# Pico_26Pin_Keyboard.net
KiCad netlist of a schematic drawn in EAGLE
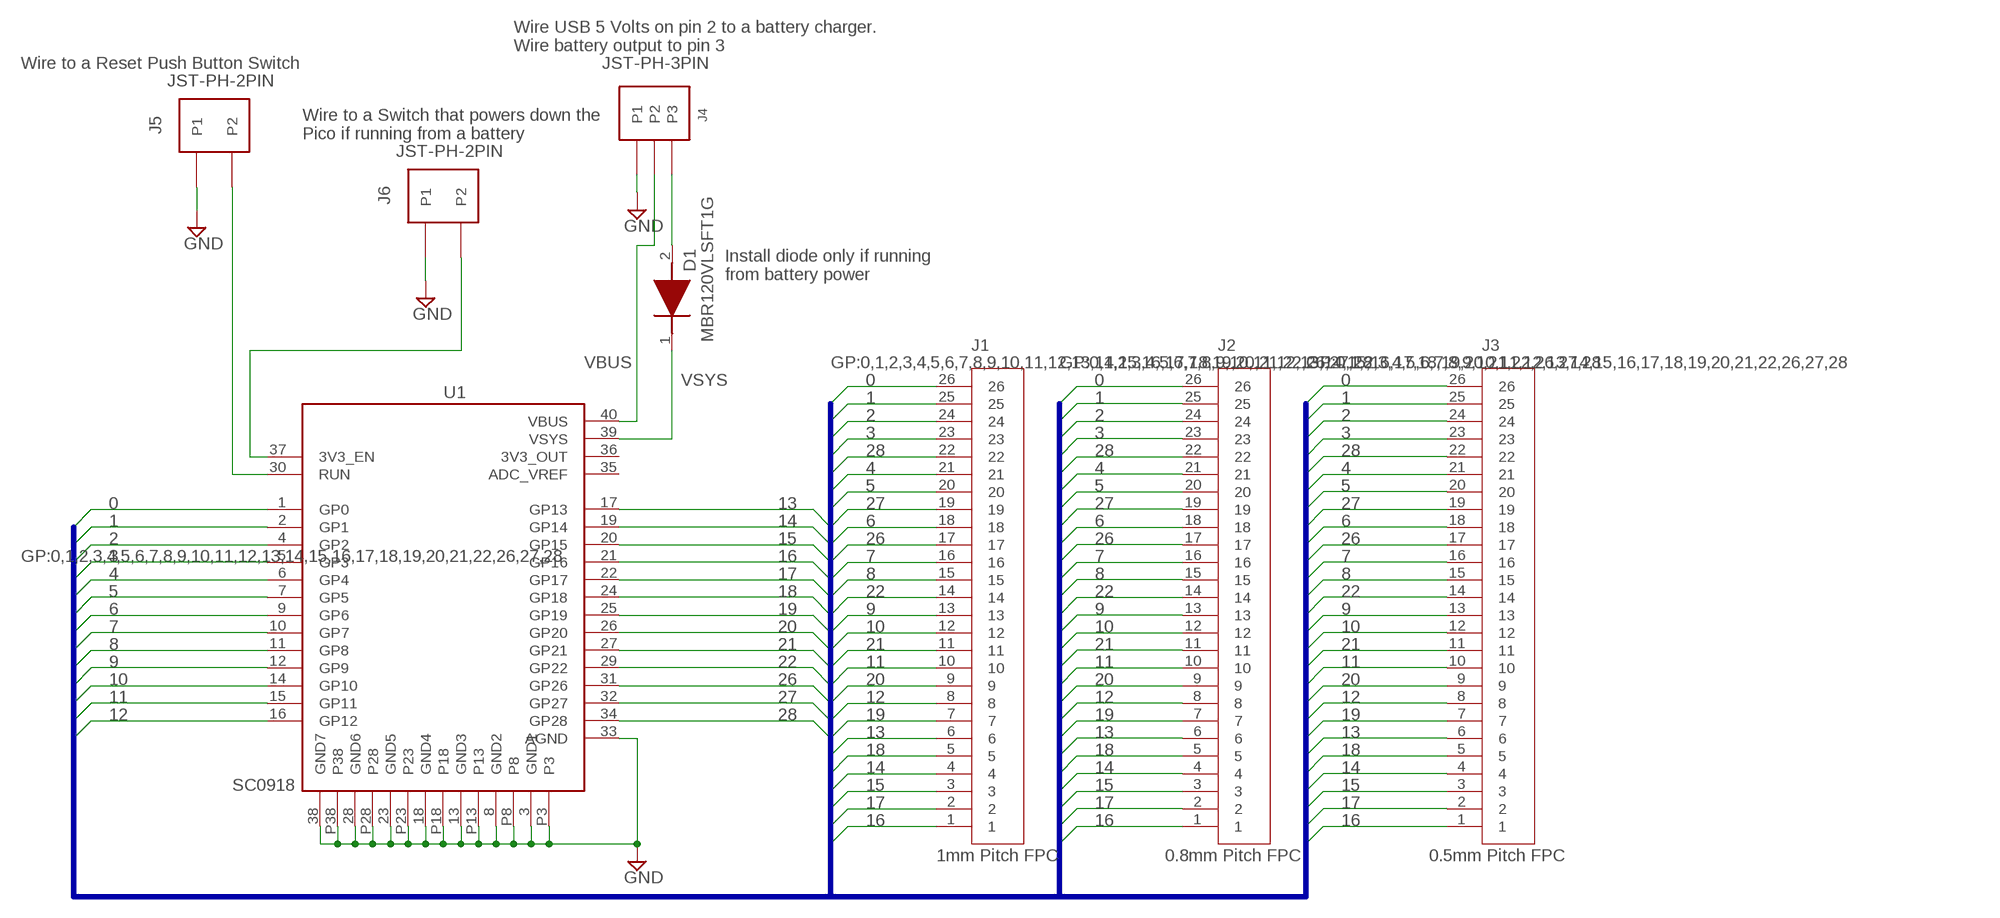
[diagram p0: schematic, sheet 1]

(export (version "E")
  (design (tool "Eeschema 10.0.6"))
  (components
    (comp (ref "D1")
      (value "MBR120VLSFT1G")
      (footprint "eagle-import:SODFL3616X98N")
      (fields (field (name "MOUSER_PART_NUMBER") "863-MBR120VLSFT1G"))
      (libsource (lib "eagle-import") (part "MBR120VLSFT1G"))
    )
    (comp (ref "J1")
      (value "1mm Pitch FPC")
      (footprint "eagle-import:FPC26")
      (libsource (lib "eagle-import") (part "FPC26"))
    )
    (comp (ref "J2")
      (value "0.8mm Pitch FPC")
      (footprint "eagle-import:FPC26_P8MM")
      (libsource (lib "eagle-import") (part "FPC26_P8MM"))
    )
    (comp (ref "J3")
      (value "0.5mm Pitch FPC")
      (footprint "eagle-import:FPC26_P5MM")
      (libsource (lib "eagle-import") (part "FPC26_P5MM"))
    )
    (comp (ref "J4")
      (value "JST-PH-3PIN")
      (footprint "eagle-import:JST-PH-3PIN")
      (libsource (lib "eagle-import") (part "JST-PH-3PIN"))
    )
    (comp (ref "J5")
      (value "JST-PH-2PIN")
      (footprint "eagle-import:JST-PH-2PIN")
      (libsource (lib "eagle-import") (part "JST-PH-2PIN"))
    )
    (comp (ref "J6")
      (value "JST-PH-2PIN")
      (footprint "eagle-import:JST-PH-2PIN")
      (libsource (lib "eagle-import") (part "JST-PH-2PIN"))
    )
    (comp (ref "U1")
      (value "SC0918")
      (footprint "eagle-import:MODULE_SC0918")
      (fields (field (name "MF") "Raspberry Pi"))
      (libsource (lib "eagle-import") (part "SC0918"))
    )
  )
  (nets
    (net (code "2") (name "/0") (class "Default")
      (node (ref "J1") (pin "26") (pinfunction "26_26") (pintype "bidirectional"))
      (node (ref "J2") (pin "26") (pinfunction "26_26") (pintype "bidirectional"))
      (node (ref "J3") (pin "26") (pinfunction "26_26") (pintype "bidirectional"))
      (node (ref "U1") (pin "1") (pinfunction "GP0_1") (pintype "bidirectional"))
    )
    (net (code "3") (name "/1") (class "Default")
      (node (ref "J1") (pin "25") (pinfunction "25_25") (pintype "bidirectional"))
      (node (ref "J2") (pin "25") (pinfunction "25_25") (pintype "bidirectional"))
      (node (ref "J3") (pin "25") (pinfunction "25_25") (pintype "bidirectional"))
      (node (ref "U1") (pin "2") (pinfunction "GP1_2") (pintype "bidirectional"))
    )
    (net (code "4") (name "/2") (class "Default")
      (node (ref "J1") (pin "24") (pinfunction "24_24") (pintype "bidirectional"))
      (node (ref "J2") (pin "24") (pinfunction "24_24") (pintype "bidirectional"))
      (node (ref "J3") (pin "24") (pinfunction "24_24") (pintype "bidirectional"))
      (node (ref "U1") (pin "4") (pinfunction "GP2_4") (pintype "bidirectional"))
    )
    (net (code "5") (name "/3") (class "Default")
      (node (ref "J1") (pin "23") (pinfunction "23_23") (pintype "bidirectional"))
      (node (ref "J2") (pin "23") (pinfunction "23_23") (pintype "bidirectional"))
      (node (ref "J3") (pin "23") (pinfunction "23_23") (pintype "bidirectional"))
      (node (ref "U1") (pin "5") (pinfunction "GP3_5") (pintype "bidirectional"))
    )
    (net (code "6") (name "/3V3_OUT") (class "Default")
      (node (ref "U1") (pin "36") (pinfunction "3V3_OUT_36") (pintype "power_in"))
    )
    (net (code "7") (name "/4") (class "Default")
      (node (ref "J1") (pin "21") (pinfunction "21_21") (pintype "bidirectional"))
      (node (ref "J2") (pin "21") (pinfunction "21_21") (pintype "bidirectional"))
      (node (ref "J3") (pin "21") (pinfunction "21_21") (pintype "bidirectional"))
      (node (ref "U1") (pin "6") (pinfunction "GP4_6") (pintype "bidirectional"))
    )
    (net (code "8") (name "/5") (class "Default")
      (node (ref "J1") (pin "20") (pinfunction "20_20") (pintype "bidirectional"))
      (node (ref "J2") (pin "20") (pinfunction "20_20") (pintype "bidirectional"))
      (node (ref "J3") (pin "20") (pinfunction "20_20") (pintype "bidirectional"))
      (node (ref "U1") (pin "7") (pinfunction "GP5_7") (pintype "bidirectional"))
    )
    (net (code "9") (name "/6") (class "Default")
      (node (ref "J1") (pin "18") (pinfunction "18_18") (pintype "bidirectional"))
      (node (ref "J2") (pin "18") (pinfunction "18_18") (pintype "bidirectional"))
      (node (ref "J3") (pin "18") (pinfunction "18_18") (pintype "bidirectional"))
      (node (ref "U1") (pin "9") (pinfunction "GP6_9") (pintype "bidirectional"))
    )
    (net (code "10") (name "/7") (class "Default")
      (node (ref "J1") (pin "16") (pinfunction "16_16") (pintype "bidirectional"))
      (node (ref "J2") (pin "16") (pinfunction "16_16") (pintype "bidirectional"))
      (node (ref "J3") (pin "16") (pinfunction "16_16") (pintype "bidirectional"))
      (node (ref "U1") (pin "10") (pinfunction "GP7_10") (pintype "bidirectional"))
    )
    (net (code "11") (name "/8") (class "Default")
      (node (ref "J1") (pin "15") (pinfunction "15_15") (pintype "bidirectional"))
      (node (ref "J2") (pin "15") (pinfunction "15_15") (pintype "bidirectional"))
      (node (ref "J3") (pin "15") (pinfunction "15_15") (pintype "bidirectional"))
      (node (ref "U1") (pin "11") (pinfunction "GP8_11") (pintype "bidirectional"))
    )
    (net (code "12") (name "/9") (class "Default")
      (node (ref "J1") (pin "13") (pinfunction "13_13") (pintype "bidirectional"))
      (node (ref "J2") (pin "13") (pinfunction "13_13") (pintype "bidirectional"))
      (node (ref "J3") (pin "13") (pinfunction "13_13") (pintype "bidirectional"))
      (node (ref "U1") (pin "12") (pinfunction "GP9_12") (pintype "bidirectional"))
    )
    (net (code "13") (name "/10") (class "Default")
      (node (ref "J1") (pin "12") (pinfunction "12_12") (pintype "bidirectional"))
      (node (ref "J2") (pin "12") (pinfunction "12_12") (pintype "bidirectional"))
      (node (ref "J3") (pin "12") (pinfunction "12_12") (pintype "bidirectional"))
      (node (ref "U1") (pin "14") (pinfunction "GP10_14") (pintype "bidirectional"))
    )
    (net (code "14") (name "/11") (class "Default")
      (node (ref "J1") (pin "10") (pinfunction "10_10") (pintype "bidirectional"))
      (node (ref "J2") (pin "10") (pinfunction "10_10") (pintype "bidirectional"))
      (node (ref "J3") (pin "10") (pinfunction "10_10") (pintype "bidirectional"))
      (node (ref "U1") (pin "15") (pinfunction "GP11_15") (pintype "bidirectional"))
    )
    (net (code "15") (name "/12") (class "Default")
      (node (ref "J1") (pin "8") (pinfunction "8_8") (pintype "bidirectional"))
      (node (ref "J2") (pin "8") (pinfunction "8_8") (pintype "bidirectional"))
      (node (ref "J3") (pin "8") (pinfunction "8_8") (pintype "bidirectional"))
      (node (ref "U1") (pin "16") (pinfunction "GP12_16") (pintype "bidirectional"))
    )
    (net (code "16") (name "/13") (class "Default")
      (node (ref "J1") (pin "6") (pinfunction "6_6") (pintype "bidirectional"))
      (node (ref "J2") (pin "6") (pinfunction "6_6") (pintype "bidirectional"))
      (node (ref "J3") (pin "6") (pinfunction "6_6") (pintype "bidirectional"))
      (node (ref "U1") (pin "17") (pinfunction "GP13_17") (pintype "bidirectional"))
    )
    (net (code "17") (name "/14") (class "Default")
      (node (ref "J1") (pin "4") (pinfunction "4_4") (pintype "bidirectional"))
      (node (ref "J2") (pin "4") (pinfunction "4_4") (pintype "bidirectional"))
      (node (ref "J3") (pin "4") (pinfunction "4_4") (pintype "bidirectional"))
      (node (ref "U1") (pin "19") (pinfunction "GP14_19") (pintype "bidirectional"))
    )
    (net (code "18") (name "/15") (class "Default")
      (node (ref "J1") (pin "3") (pinfunction "3_3") (pintype "bidirectional"))
      (node (ref "J2") (pin "3") (pinfunction "3_3") (pintype "bidirectional"))
      (node (ref "J3") (pin "3") (pinfunction "3_3") (pintype "bidirectional"))
      (node (ref "U1") (pin "20") (pinfunction "GP15_20") (pintype "bidirectional"))
    )
    (net (code "19") (name "/16") (class "Default")
      (node (ref "J1") (pin "1") (pinfunction "1_1") (pintype "bidirectional"))
      (node (ref "J2") (pin "1") (pinfunction "1_1") (pintype "bidirectional"))
      (node (ref "J3") (pin "1") (pinfunction "1_1") (pintype "bidirectional"))
      (node (ref "U1") (pin "21") (pinfunction "GP16_21") (pintype "bidirectional"))
    )
    (net (code "20") (name "/17") (class "Default")
      (node (ref "J1") (pin "2") (pinfunction "2_2") (pintype "bidirectional"))
      (node (ref "J2") (pin "2") (pinfunction "2_2") (pintype "bidirectional"))
      (node (ref "J3") (pin "2") (pinfunction "2_2") (pintype "bidirectional"))
      (node (ref "U1") (pin "22") (pinfunction "GP17_22") (pintype "bidirectional"))
    )
    (net (code "21") (name "/18") (class "Default")
      (node (ref "J1") (pin "5") (pinfunction "5_5") (pintype "bidirectional"))
      (node (ref "J2") (pin "5") (pinfunction "5_5") (pintype "bidirectional"))
      (node (ref "J3") (pin "5") (pinfunction "5_5") (pintype "bidirectional"))
      (node (ref "U1") (pin "24") (pinfunction "GP18_24") (pintype "bidirectional"))
    )
    (net (code "22") (name "/19") (class "Default")
      (node (ref "J1") (pin "7") (pinfunction "7_7") (pintype "bidirectional"))
      (node (ref "J2") (pin "7") (pinfunction "7_7") (pintype "bidirectional"))
      (node (ref "J3") (pin "7") (pinfunction "7_7") (pintype "bidirectional"))
      (node (ref "U1") (pin "25") (pinfunction "GP19_25") (pintype "bidirectional"))
    )
    (net (code "23") (name "/20") (class "Default")
      (node (ref "J1") (pin "9") (pinfunction "9_9") (pintype "bidirectional"))
      (node (ref "J2") (pin "9") (pinfunction "9_9") (pintype "bidirectional"))
      (node (ref "J3") (pin "9") (pinfunction "9_9") (pintype "bidirectional"))
      (node (ref "U1") (pin "26") (pinfunction "GP20_26") (pintype "bidirectional"))
    )
    (net (code "24") (name "/21") (class "Default")
      (node (ref "J1") (pin "11") (pinfunction "11_11") (pintype "bidirectional"))
      (node (ref "J2") (pin "11") (pinfunction "11_11") (pintype "bidirectional"))
      (node (ref "J3") (pin "11") (pinfunction "11_11") (pintype "bidirectional"))
      (node (ref "U1") (pin "27") (pinfunction "GP21_27") (pintype "bidirectional"))
    )
    (net (code "25") (name "/22") (class "Default")
      (node (ref "J1") (pin "14") (pinfunction "14_14") (pintype "bidirectional"))
      (node (ref "J2") (pin "14") (pinfunction "14_14") (pintype "bidirectional"))
      (node (ref "J3") (pin "14") (pinfunction "14_14") (pintype "bidirectional"))
      (node (ref "U1") (pin "29") (pinfunction "GP22_29") (pintype "bidirectional"))
    )
    (net (code "26") (name "/26") (class "Default")
      (node (ref "J1") (pin "17") (pinfunction "17_17") (pintype "bidirectional"))
      (node (ref "J2") (pin "17") (pinfunction "17_17") (pintype "bidirectional"))
      (node (ref "J3") (pin "17") (pinfunction "17_17") (pintype "bidirectional"))
      (node (ref "U1") (pin "31") (pinfunction "GP26_31") (pintype "bidirectional"))
    )
    (net (code "27") (name "/27") (class "Default")
      (node (ref "J1") (pin "19") (pinfunction "19_19") (pintype "bidirectional"))
      (node (ref "J2") (pin "19") (pinfunction "19_19") (pintype "bidirectional"))
      (node (ref "J3") (pin "19") (pinfunction "19_19") (pintype "bidirectional"))
      (node (ref "U1") (pin "32") (pinfunction "GP27_32") (pintype "bidirectional"))
    )
    (net (code "28") (name "/28") (class "Default")
      (node (ref "J1") (pin "22") (pinfunction "22_22") (pintype "bidirectional"))
      (node (ref "J2") (pin "22") (pinfunction "22_22") (pintype "bidirectional"))
      (node (ref "J3") (pin "22") (pinfunction "22_22") (pintype "bidirectional"))
      (node (ref "U1") (pin "34") (pinfunction "GP28_34") (pintype "bidirectional"))
    )
    (net (code "29") (name "/ADC_VREF") (class "Default")
      (node (ref "U1") (pin "35") (pinfunction "ADC_VREF_35") (pintype "power_in"))
    )
    (net (code "30") (name "/VBUS") (class "Default")
      (node (ref "J4") (pin "P$2") (pinfunction "P2_P$2") (pintype "bidirectional"))
      (node (ref "U1") (pin "40") (pinfunction "VBUS_40") (pintype "power_in"))
    )
    (net (code "31") (name "/VSYS") (class "Default")
      (node (ref "D1") (pin "1") (pinfunction "K_1") (pintype "bidirectional"))
      (node (ref "U1") (pin "39") (pinfunction "VSYS_39") (pintype "power_in"))
    )
    (net (code "33") (name "GND") (class "Default")
      (node (ref "J4") (pin "P$1") (pinfunction "P1_P$1") (pintype "bidirectional"))
      (node (ref "J5") (pin "P$1") (pinfunction "P1_P$1") (pintype "bidirectional"))
      (node (ref "J6") (pin "P$1") (pinfunction "P1_P$1") (pintype "bidirectional"))
      (node (ref "U1") (pin "13") (pinfunction "GND3_13") (pintype "power_in"))
      (node (ref "U1") (pin "18") (pinfunction "GND4_18") (pintype "power_in"))
      (node (ref "U1") (pin "23") (pinfunction "GND5_23") (pintype "power_in"))
      (node (ref "U1") (pin "28") (pinfunction "GND6_28") (pintype "power_in"))
      (node (ref "U1") (pin "3") (pinfunction "GND1_3") (pintype "power_in"))
      (node (ref "U1") (pin "33") (pinfunction "AGND_33") (pintype "power_in"))
      (node (ref "U1") (pin "38") (pinfunction "GND7_38") (pintype "power_in"))
      (node (ref "U1") (pin "8") (pinfunction "GND2_8") (pintype "power_in"))
      (node (ref "U1") (pin "P13") (pinfunction "P13_P13") (pintype "power_in"))
      (node (ref "U1") (pin "P18") (pinfunction "P18_P18") (pintype "power_in"))
      (node (ref "U1") (pin "P23") (pinfunction "P23_P23") (pintype "power_in"))
      (node (ref "U1") (pin "P28") (pinfunction "P28_P28") (pintype "power_in"))
      (node (ref "U1") (pin "P3") (pinfunction "P3_P3") (pintype "power_in"))
      (node (ref "U1") (pin "P38") (pinfunction "P38_P38") (pintype "power_in"))
      (node (ref "U1") (pin "P8") (pinfunction "P8_P8") (pintype "power_in"))
    )
    (net (code "34") (name "Net-(D1-A)") (class "Default")
      (node (ref "D1") (pin "2") (pinfunction "A_2") (pintype "bidirectional"))
      (node (ref "J4") (pin "P$3") (pinfunction "P3_P$3") (pintype "bidirectional"))
    )
    (net (code "35") (name "Net-(J5-P2)") (class "Default")
      (node (ref "J5") (pin "P$2") (pinfunction "P2_P$2") (pintype "bidirectional"))
      (node (ref "U1") (pin "30") (pinfunction "RUN_30") (pintype "input"))
    )
    (net (code "36") (name "Net-(J6-P2)") (class "Default")
      (node (ref "J6") (pin "P$2") (pinfunction "P2_P$2") (pintype "bidirectional"))
      (node (ref "U1") (pin "37") (pinfunction "3V3_EN_37") (pintype "input"))
    )
  )
)
